# Storage.net
KiCad netlist of a schematic drawn in Altium Designer
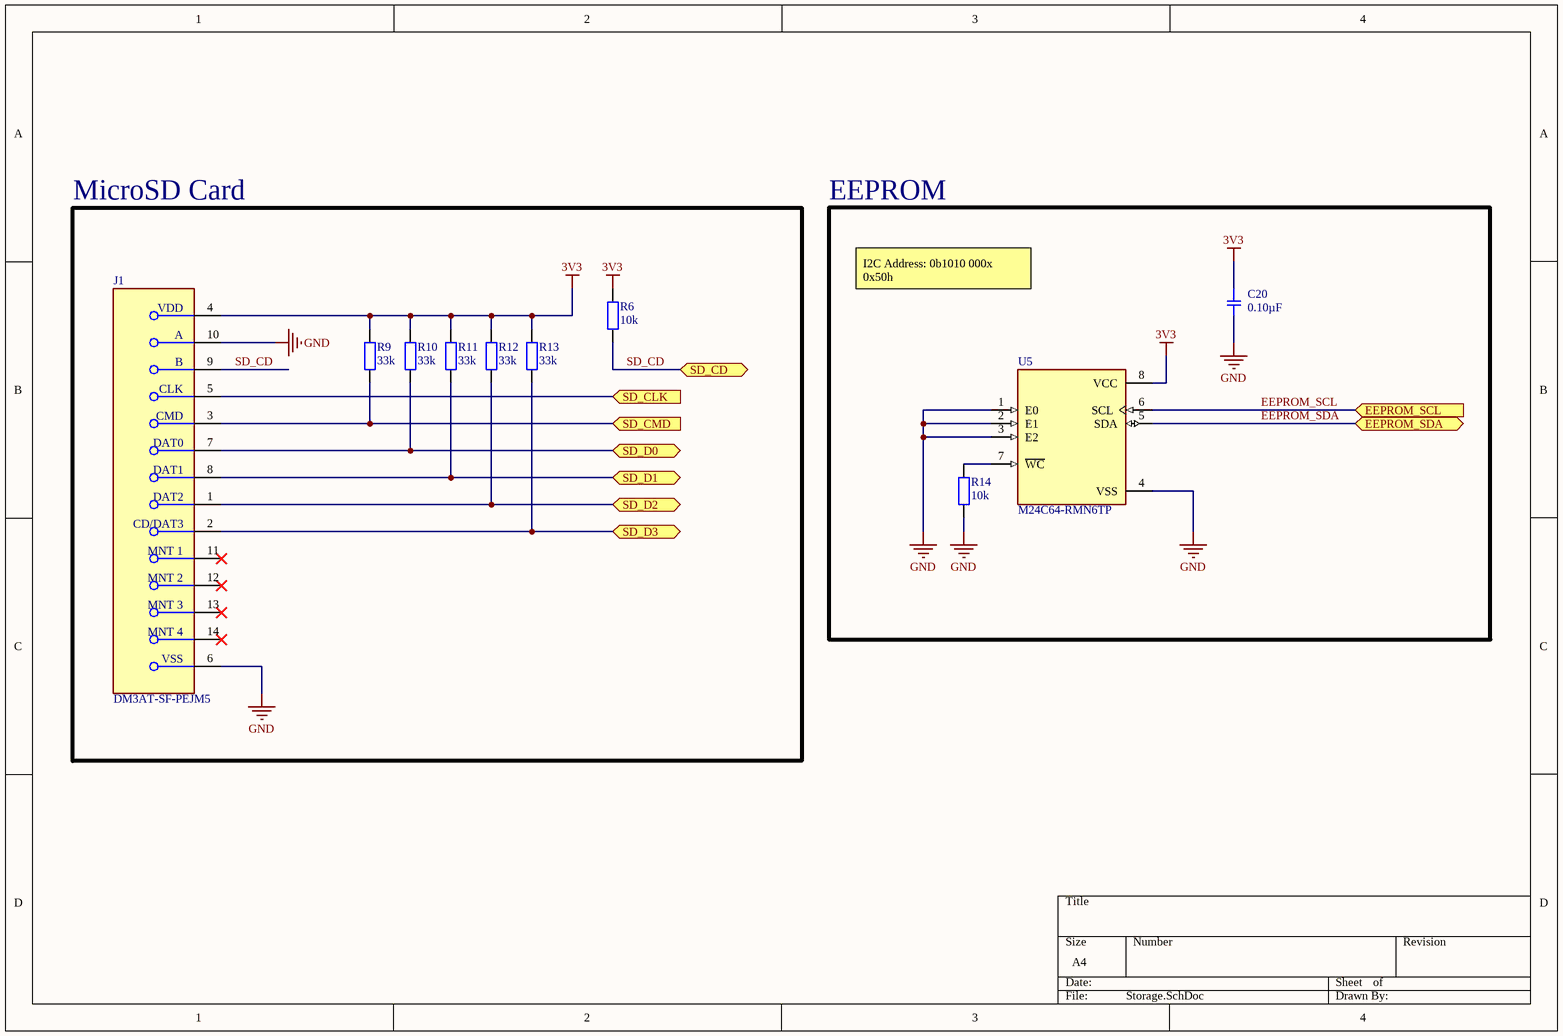
[diagram p0: Storage.SchDoc]

(export (version "E")
  (design (tool "Eeschema 10.0.6"))
  (components
    (comp (ref "C20")
      (value "0.10µF")
      (footprint "SMD-0402C")
      (description "CAP CER 0.1UF 10V X5R 0402")
      (fields (field (name "DIGI-KEY PART NUMBER") "490-6297-1-ND") (field (name "VOLTAGE") "10V"))
      (libsource (lib "University of British Columbia") (part "ZRB15XR61A475ME01D"))
    )
    (comp (ref "J1")
      (value "DM3AT-SF-PEJM5")
      (footprint "FP-DM3AT-SF-PEJM5-MFG")
      (description "CONN MICRO SD CARD PUSH-PUSH R/A")
      (libsource (lib "Altium Content Vault") (part "a4e64ec0820c4377148bc1329e4c440"))
    )
    (comp (ref "R6")
      (value "10k")
      (footprint "IPC C R0402 NO SILK")
      (libsource (lib "Jack Kelly") (part "Generic RES 0603"))
    )
    (comp (ref "R9")
      (value "33k")
      (footprint "IPC C R0402 NO SILK")
      (libsource (lib "Jack Kelly") (part "Generic RES 0603"))
    )
    (comp (ref "R10")
      (value "33k")
      (footprint "IPC C R0402 NO SILK")
      (libsource (lib "Jack Kelly") (part "Generic RES 0603"))
    )
    (comp (ref "R11")
      (value "33k")
      (footprint "IPC C R0402 NO SILK")
      (libsource (lib "Jack Kelly") (part "Generic RES 0603"))
    )
    (comp (ref "R12")
      (value "33k")
      (footprint "IPC C R0402 NO SILK")
      (libsource (lib "Jack Kelly") (part "Generic RES 0603"))
    )
    (comp (ref "R13")
      (value "33k")
      (footprint "IPC C R0402 NO SILK")
      (libsource (lib "Jack Kelly") (part "Generic RES 0603"))
    )
    (comp (ref "R14")
      (value "10k")
      (footprint "IPC C R0402 NO SILK")
      (libsource (lib "Jack Kelly") (part "Generic RES 0603"))
    )
    (comp (ref "U5")
      (value "M24C64-RMN6TP")
      (footprint "SOIC127P600X175-8N")
      (libsource (lib "Jack Kelly") (part "M24C64-RMN6TP"))
    )
  )
  (nets
    (net (code "1") (name "/EEPROM_SCL") (class "Default")
      (node (ref "U5") (pin "6") (pinfunction "SCL_6") (pintype "input"))
    )
    (net (code "2") (name "/EEPROM_SDA") (class "Default")
      (node (ref "U5") (pin "5") (pinfunction "SDA_5") (pintype "bidirectional"))
    )
    (net (code "3") (name "/SD_CD") (class "Default")
      (node (ref "J1") (pin "9") (pinfunction "B_9") (pintype "passive"))
      (node (ref "R6") (pin "1") (pinfunction "1_1") (pintype "passive"))
    )
    (net (code "4") (name "/SD_CLK") (class "Default")
      (node (ref "J1") (pin "5") (pinfunction "CLK_5") (pintype "passive"))
    )
    (net (code "5") (name "/SD_CMD") (class "Default")
      (node (ref "J1") (pin "3") (pinfunction "CMD_3") (pintype "passive"))
      (node (ref "R9") (pin "1") (pinfunction "1_1") (pintype "passive"))
    )
    (net (code "6") (name "/SD_D0") (class "Default")
      (node (ref "J1") (pin "7") (pinfunction "DAT0_7") (pintype "passive"))
      (node (ref "R10") (pin "1") (pinfunction "1_1") (pintype "passive"))
    )
    (net (code "7") (name "/SD_D1") (class "Default")
      (node (ref "J1") (pin "8") (pinfunction "DAT1_8") (pintype "passive"))
      (node (ref "R11") (pin "1") (pinfunction "1_1") (pintype "passive"))
    )
    (net (code "8") (name "/SD_D2") (class "Default")
      (node (ref "J1") (pin "1") (pinfunction "DAT2_1") (pintype "passive"))
      (node (ref "R12") (pin "1") (pinfunction "1_1") (pintype "passive"))
    )
    (net (code "9") (name "/SD_D3") (class "Default")
      (node (ref "J1") (pin "2") (pinfunction "CD/DAT3_2") (pintype "passive"))
      (node (ref "R13") (pin "1") (pinfunction "1_1") (pintype "passive"))
    )
    (net (code "10") (name "3V3") (class "Default")
      (node (ref "C20") (pin "1") (pinfunction "1_1") (pintype "passive"))
      (node (ref "J1") (pin "4") (pinfunction "VDD_4") (pintype "power_in"))
      (node (ref "R10") (pin "2") (pinfunction "2_2") (pintype "passive"))
      (node (ref "R11") (pin "2") (pinfunction "2_2") (pintype "passive"))
      (node (ref "R12") (pin "2") (pinfunction "2_2") (pintype "passive"))
      (node (ref "R13") (pin "2") (pinfunction "2_2") (pintype "passive"))
      (node (ref "R6") (pin "2") (pinfunction "2_2") (pintype "passive"))
      (node (ref "R9") (pin "2") (pinfunction "2_2") (pintype "passive"))
      (node (ref "U5") (pin "8") (pinfunction "VCC_8") (pintype "power_in"))
    )
    (net (code "11") (name "GND") (class "Default")
      (node (ref "C20") (pin "2") (pinfunction "2_2") (pintype "passive"))
      (node (ref "J1") (pin "10") (pinfunction "A_10") (pintype "passive"))
      (node (ref "J1") (pin "6") (pinfunction "VSS_6") (pintype "power_in"))
      (node (ref "R14") (pin "2") (pinfunction "2_2") (pintype "passive"))
      (node (ref "U5") (pin "1") (pinfunction "E0_1") (pintype "input"))
      (node (ref "U5") (pin "2") (pinfunction "E1_2") (pintype "input"))
      (node (ref "U5") (pin "3") (pinfunction "E2_3") (pintype "input"))
      (node (ref "U5") (pin "4") (pinfunction "VSS_4") (pintype "power_in"))
    )
    (net (code "12") (name "Net-(U5-~{WC})") (class "Default")
      (node (ref "R14") (pin "1") (pinfunction "1_1") (pintype "passive"))
      (node (ref "U5") (pin "7") (pinfunction "~{WC}_7") (pintype "input"))
    )
    (net (code "13") (name "unconnected-(J1-MNT_1-Pad11)") (class "Default")
      (node (ref "J1") (pin "11") (pinfunction "MNT_1_11") (pintype "passive+no_connect"))
    )
    (net (code "14") (name "unconnected-(J1-MNT_2-Pad12)") (class "Default")
      (node (ref "J1") (pin "12") (pinfunction "MNT_2_12") (pintype "passive+no_connect"))
    )
    (net (code "15") (name "unconnected-(J1-MNT_3-Pad13)") (class "Default")
      (node (ref "J1") (pin "13") (pinfunction "MNT_3_13") (pintype "passive+no_connect"))
    )
    (net (code "16") (name "unconnected-(J1-MNT_4-Pad14)") (class "Default")
      (node (ref "J1") (pin "14") (pinfunction "MNT_4_14") (pintype "passive+no_connect"))
    )
  )
)
